# Analog_Buffer.net
KiCad netlist of a schematic drawn in Altium Designer
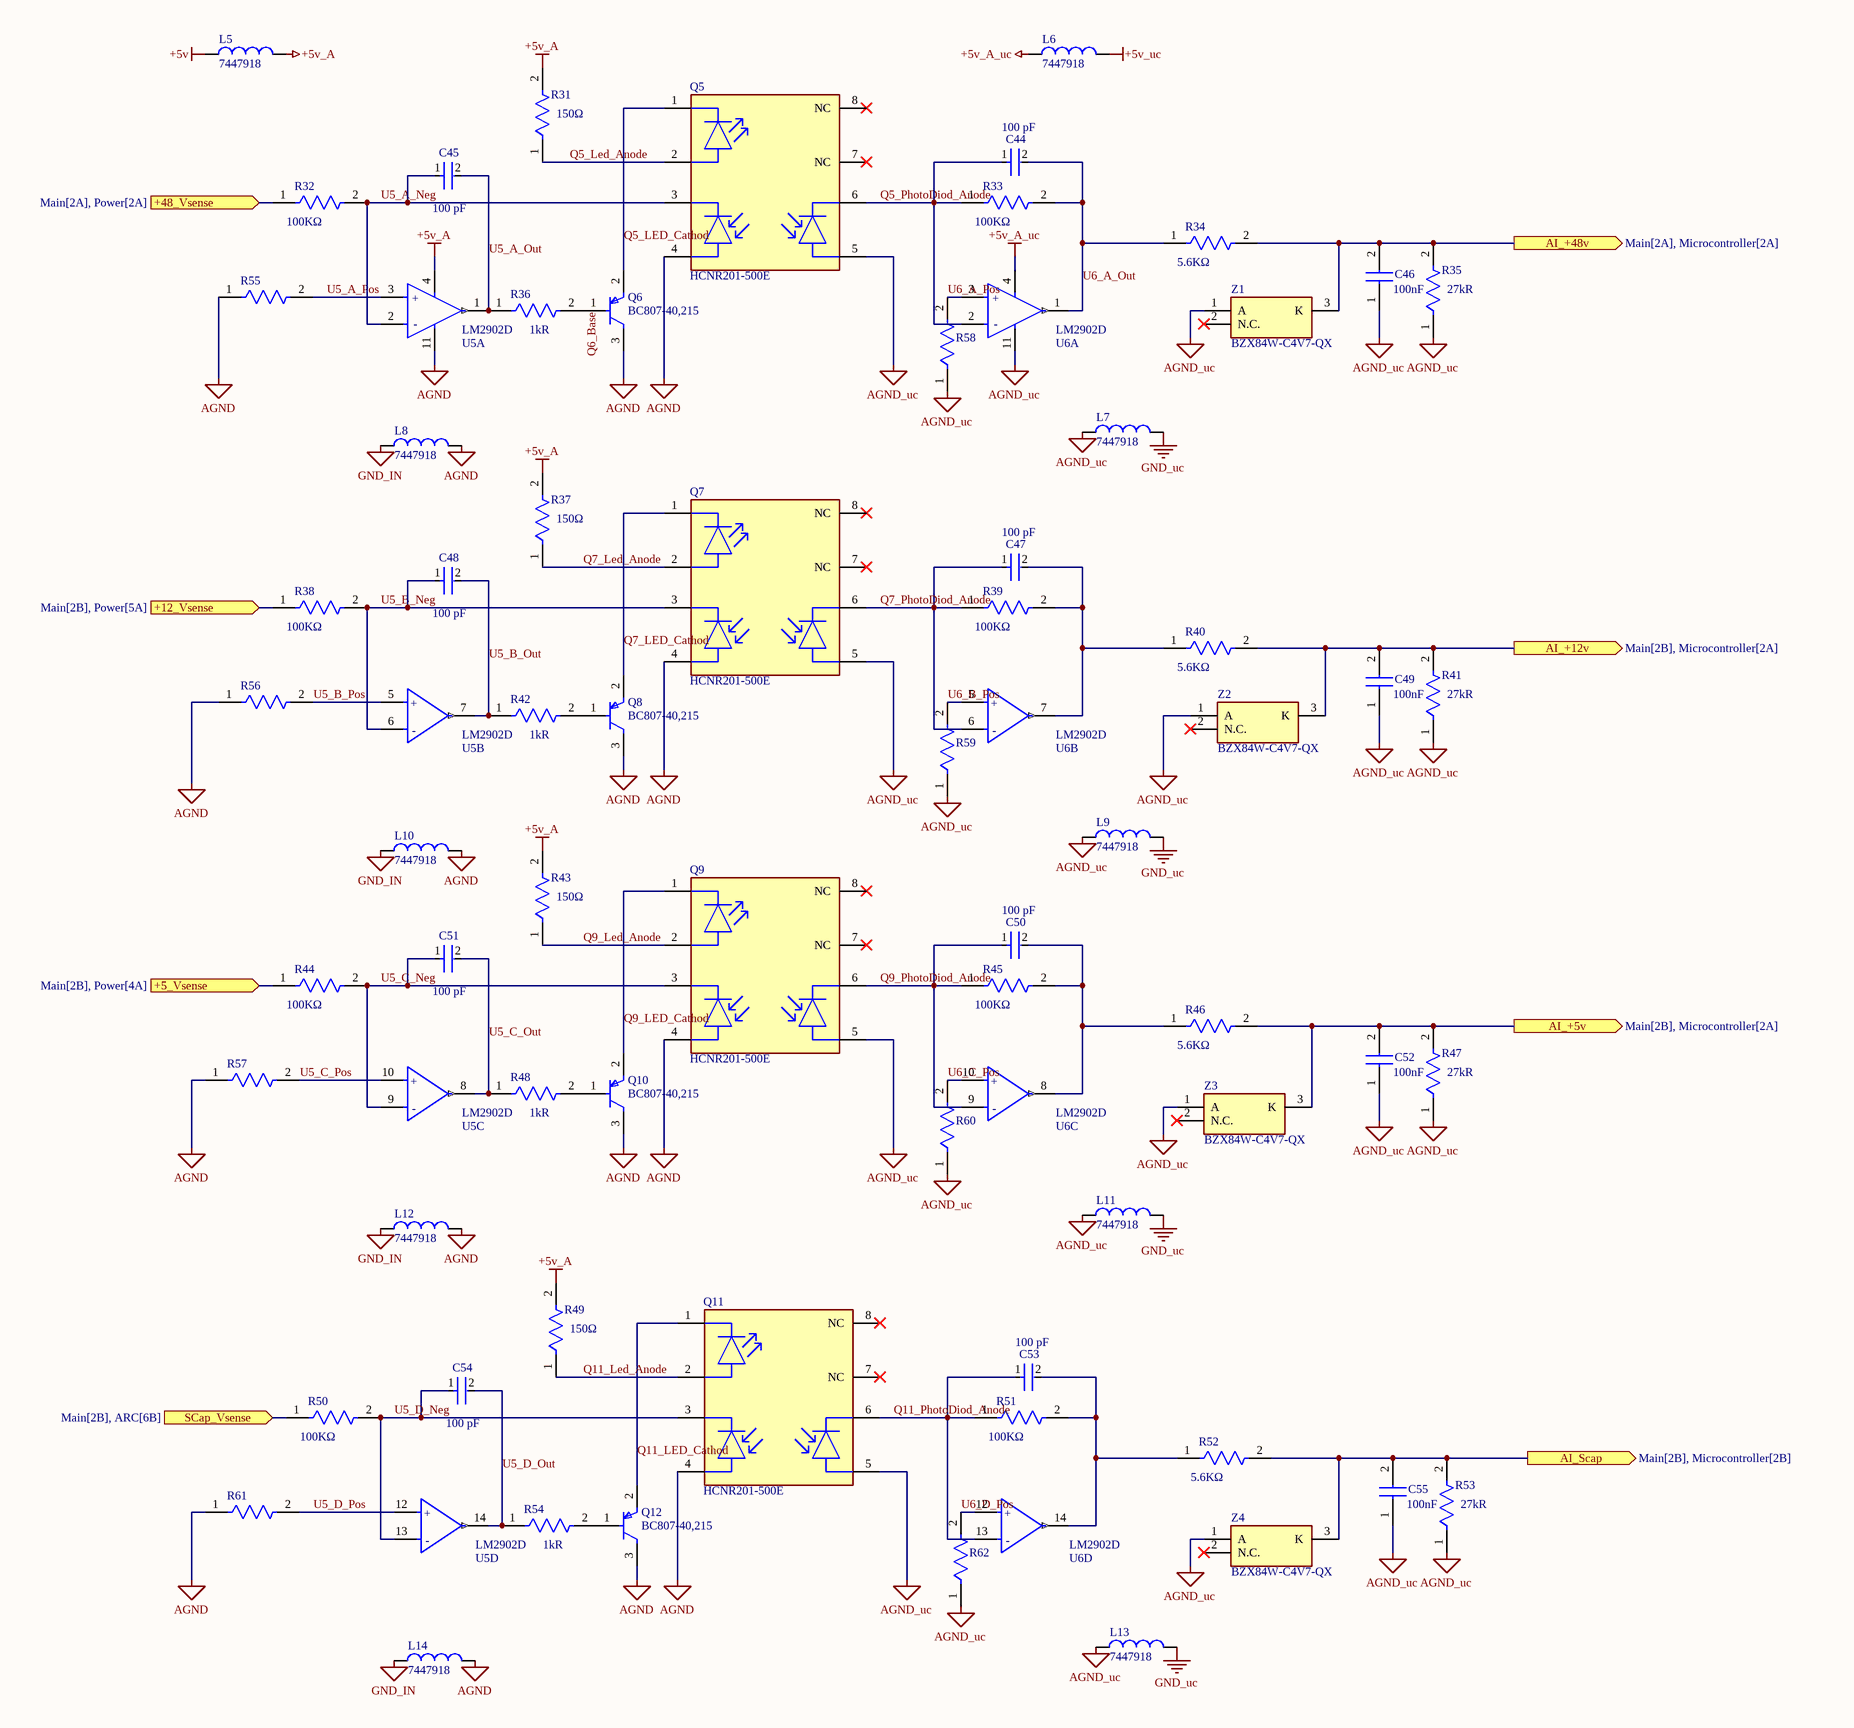
[diagram p0: Analog_Buffer.SchDoc]

(export (version "E")
  (design (tool "Eeschema 10.0.6"))
  (components
    (comp (ref "C44")
      (value "100 pF")
      (footprint "FP-C1206C-EB-MFG")
      (description "CAP CER 100PF 50V 10% NP0 1206")
      (fields
        (field (name "OCTOPART") "https://octopart.com/c1206c101k5gactu-kemet-9138650")
        (field (name "TOLERANCE") "0.1")
      )
      (libsource (lib "Altium Content Vault") (part "b4654b650e69147ec39a6b967a45e02"))
    )
    (comp (ref "C45")
      (value "100 pF")
      (footprint "FP-C1206C-EB-MFG")
      (description "CAP CER 100PF 50V 10% NP0 1206")
      (fields
        (field (name "OCTOPART") "https://octopart.com/c1206c101k5gactu-kemet-9138650")
        (field (name "TOLERANCE") "0.1")
      )
      (libsource (lib "Altium Content Vault") (part "b4654b650e69147ec39a6b967a45e02"))
    )
    (comp (ref "C46")
      (value "100nF")
      (footprint "SamacSys:CAPC3216X95N")
      (description "Capacitor")
      (fields
        (field (name "MANUFACTURER_PART_NUMBER") "GRM319F51H104ZA01D")
        (field (name "MOUSER PART NUMBER") "81-GRM319F51H104ZA")
      )
      (libsource (lib "*") (part "GRM319F51H104ZA01D"))
    )
    (comp (ref "C47")
      (value "100 pF")
      (footprint "FP-C1206C-EB-MFG")
      (description "CAP CER 100PF 50V 10% NP0 1206")
      (fields
        (field (name "OCTOPART") "https://octopart.com/c1206c101k5gactu-kemet-9138650")
        (field (name "TOLERANCE") "0.1")
      )
      (libsource (lib "Altium Content Vault") (part "b4654b650e69147ec39a6b967a45e02"))
    )
    (comp (ref "C48")
      (value "100 pF")
      (footprint "FP-C1206C-EB-MFG")
      (description "CAP CER 100PF 50V 10% NP0 1206")
      (fields
        (field (name "OCTOPART") "https://octopart.com/c1206c101k5gactu-kemet-9138650")
        (field (name "TOLERANCE") "0.1")
      )
      (libsource (lib "Altium Content Vault") (part "b4654b650e69147ec39a6b967a45e02"))
    )
    (comp (ref "C49")
      (value "100nF")
      (footprint "SamacSys:CAPC3216X95N")
      (description "Capacitor")
      (fields
        (field (name "MANUFACTURER_PART_NUMBER") "GRM319F51H104ZA01D")
        (field (name "MOUSER PART NUMBER") "81-GRM319F51H104ZA")
      )
      (libsource (lib "*") (part "GRM319F51H104ZA01D"))
    )
    (comp (ref "C50")
      (value "100 pF")
      (footprint "FP-C1206C-EB-MFG")
      (description "CAP CER 100PF 50V 10% NP0 1206")
      (fields
        (field (name "OCTOPART") "https://octopart.com/c1206c101k5gactu-kemet-9138650")
        (field (name "TOLERANCE") "0.1")
      )
      (libsource (lib "Altium Content Vault") (part "b4654b650e69147ec39a6b967a45e02"))
    )
    (comp (ref "C51")
      (value "100 pF")
      (footprint "FP-C1206C-EB-MFG")
      (description "CAP CER 100PF 50V 10% NP0 1206")
      (fields
        (field (name "OCTOPART") "https://octopart.com/c1206c101k5gactu-kemet-9138650")
        (field (name "TOLERANCE") "0.1")
      )
      (libsource (lib "Altium Content Vault") (part "b4654b650e69147ec39a6b967a45e02"))
    )
    (comp (ref "C52")
      (value "100nF")
      (footprint "SamacSys:CAPC3216X95N")
      (description "Capacitor")
      (fields
        (field (name "MANUFACTURER_PART_NUMBER") "GRM319F51H104ZA01D")
        (field (name "MOUSER PART NUMBER") "81-GRM319F51H104ZA")
      )
      (libsource (lib "*") (part "GRM319F51H104ZA01D"))
    )
    (comp (ref "C53")
      (value "100 pF")
      (footprint "FP-C1206C-EB-MFG")
      (description "CAP CER 100PF 50V 10% NP0 1206")
      (fields
        (field (name "OCTOPART") "https://octopart.com/c1206c101k5gactu-kemet-9138650")
        (field (name "TOLERANCE") "0.1")
      )
      (libsource (lib "Altium Content Vault") (part "b4654b650e69147ec39a6b967a45e02"))
    )
    (comp (ref "C54")
      (value "100 pF")
      (footprint "FP-C1206C-EB-MFG")
      (description "CAP CER 100PF 50V 10% NP0 1206")
      (fields
        (field (name "OCTOPART") "https://octopart.com/c1206c101k5gactu-kemet-9138650")
        (field (name "TOLERANCE") "0.1")
      )
      (libsource (lib "Altium Content Vault") (part "b4654b650e69147ec39a6b967a45e02"))
    )
    (comp (ref "C55")
      (value "100nF")
      (footprint "SamacSys:CAPC3216X95N")
      (description "Capacitor")
      (fields
        (field (name "MANUFACTURER_PART_NUMBER") "GRM319F51H104ZA01D")
        (field (name "MOUSER PART NUMBER") "81-GRM319F51H104ZA")
      )
      (libsource (lib "*") (part "GRM319F51H104ZA01D"))
    )
    (comp (ref "L5")
      (value "7447918")
      (footprint "WE-MI_1206_L3.2W1.6H1.1")
      (fields (field (name "TOLERANCE") "10%"))
      (libsource (lib "Altium Content Vault") (part "Inductor - 1"))
    )
    (comp (ref "L6")
      (value "7447918")
      (footprint "WE-MI_1206_L3.2W1.6H1.1")
      (fields (field (name "TOLERANCE") "10%"))
      (libsource (lib "Altium Content Vault") (part "Inductor - 1"))
    )
    (comp (ref "L7")
      (value "7447918")
      (footprint "WE-MI_1206_L3.2W1.6H1.1")
      (fields (field (name "TOLERANCE") "10%"))
      (libsource (lib "Altium Content Vault") (part "Inductor - 1"))
    )
    (comp (ref "L8")
      (value "7447918")
      (footprint "WE-MI_1206_L3.2W1.6H1.1")
      (fields (field (name "TOLERANCE") "10%"))
      (libsource (lib "Altium Content Vault") (part "Inductor - 1"))
    )
    (comp (ref "L9")
      (value "7447918")
      (footprint "WE-MI_1206_L3.2W1.6H1.1")
      (fields (field (name "TOLERANCE") "10%"))
      (libsource (lib "Altium Content Vault") (part "Inductor - 1"))
    )
    (comp (ref "L10")
      (value "7447918")
      (footprint "WE-MI_1206_L3.2W1.6H1.1")
      (fields (field (name "TOLERANCE") "10%"))
      (libsource (lib "Altium Content Vault") (part "Inductor - 1"))
    )
    (comp (ref "L11")
      (value "7447918")
      (footprint "WE-MI_1206_L3.2W1.6H1.1")
      (fields (field (name "TOLERANCE") "10%"))
      (libsource (lib "Altium Content Vault") (part "Inductor - 1"))
    )
    (comp (ref "L12")
      (value "7447918")
      (footprint "WE-MI_1206_L3.2W1.6H1.1")
      (fields (field (name "TOLERANCE") "10%"))
      (libsource (lib "Altium Content Vault") (part "Inductor - 1"))
    )
    (comp (ref "L13")
      (value "7447918")
      (footprint "WE-MI_1206_L3.2W1.6H1.1")
      (fields (field (name "TOLERANCE") "10%"))
      (libsource (lib "Altium Content Vault") (part "Inductor - 1"))
    )
    (comp (ref "L14")
      (value "7447918")
      (footprint "WE-MI_1206_L3.2W1.6H1.1")
      (fields (field (name "TOLERANCE") "10%"))
      (libsource (lib "Altium Content Vault") (part "Inductor - 1"))
    )
    (comp (ref "Q5")
      (value "HCNR201-500E")
      (footprint "FP-HCNR201-500E-MFG")
      (description "OPTOISO 5KV LINEAR PHVOLT 8DIPGW")
      (libsource (lib "Altium Content Vault") (part "91ab35065b22d0708acdc738a14b8cf"))
    )
    (comp (ref "Q6")
      (value "BC807-40,215")
      (footprint "FP-SOT23-IPC_B")
      (description "TRANS PNP 45V 500MA TO236AB")
      (libsource (lib "Altium Content Vault") (part "0e8486ed3b47d9c69b8404ba87cf0f7"))
    )
    (comp (ref "Q7")
      (value "HCNR201-500E")
      (footprint "FP-HCNR201-500E-MFG")
      (description "OPTOISO 5KV LINEAR PHVOLT 8DIPGW")
      (libsource (lib "Altium Content Vault") (part "91ab35065b22d0708acdc738a14b8cf"))
    )
    (comp (ref "Q8")
      (value "BC807-40,215")
      (footprint "FP-SOT23-IPC_B")
      (description "TRANS PNP 45V 500MA TO236AB")
      (libsource (lib "Altium Content Vault") (part "0e8486ed3b47d9c69b8404ba87cf0f7"))
    )
    (comp (ref "Q9")
      (value "HCNR201-500E")
      (footprint "FP-HCNR201-500E-MFG")
      (description "OPTOISO 5KV LINEAR PHVOLT 8DIPGW")
      (libsource (lib "Altium Content Vault") (part "91ab35065b22d0708acdc738a14b8cf"))
    )
    (comp (ref "Q10")
      (value "BC807-40,215")
      (footprint "FP-SOT23-IPC_B")
      (description "TRANS PNP 45V 500MA TO236AB")
      (libsource (lib "Altium Content Vault") (part "0e8486ed3b47d9c69b8404ba87cf0f7"))
    )
    (comp (ref "Q11")
      (value "HCNR201-500E")
      (footprint "FP-HCNR201-500E-MFG")
      (description "OPTOISO 5KV LINEAR PHVOLT 8DIPGW")
      (libsource (lib "Altium Content Vault") (part "91ab35065b22d0708acdc738a14b8cf"))
    )
    (comp (ref "Q12")
      (value "BC807-40,215")
      (footprint "FP-SOT23-IPC_B")
      (description "TRANS PNP 45V 500MA TO236AB")
      (libsource (lib "Altium Content Vault") (part "0e8486ed3b47d9c69b8404ba87cf0f7"))
    )
    (comp (ref "R31")
      (value "RP73D2B150RBTG")
      (footprint "FP-RP732B-MFG")
      (description "Res Thin Film 1206 150Ω 0.1% 0.25W 15ppm/°C Molded SMD")
      (fields
        (field (name "MANUFACTURER") "TE Connectivity")
        (field (name "RESISTANCE") "150Ω")
        (field (name "TOLERANCE") "0.1%")
      )
      (libsource (lib "Altium Content Vault") (part "1029c3af85768c4190bb7ad29bc67b5"))
    )
    (comp (ref "R32")
      (value "100KΩ")
      (footprint "FP-RT1206-MFG")
      (description "RES SMD 100K OHM 0.5% 1/4W 1206")
      (fields
        (field (name "MANUFACTURER") "Yageo")
        (field (name "OCTOPART") "https://octopart.com/rt1206dre07100kl-yageo-1189867")
      )
      (libsource (lib "Altium Content Vault") (part "1029c3af85768c4190bb7ad29bc67b5"))
    )
    (comp (ref "R33")
      (value "100KΩ")
      (footprint "FP-RT1206-MFG")
      (description "RES SMD 100K OHM 0.5% 1/4W 1206")
      (fields
        (field (name "MANUFACTURER") "Yageo")
        (field (name "OCTOPART") "https://octopart.com/rt1206dre07100kl-yageo-1189867")
      )
      (libsource (lib "Altium Content Vault") (part "1029c3af85768c4190bb7ad29bc67b5"))
    )
    (comp (ref "R34")
      (value "5.6KΩ")
      (footprint "FP-CRGP1206-IPC_C")
      (description "CRGP 1206 5K6 1%")
      (fields (field (name "TOLERANCE") "0.01") (field (name "MANUFACTURER PART NUMBER") "CRGP1206F5K6"))
      (libsource (lib "Altium Content Vault") (part "1029c3af85768c4190bb7ad29bc67b5"))
    )
    (comp (ref "R35")
      (value "RC3216J273CS")
      (footprint "FP-RC3216-IPC_A")
      (description "Res Thick Film 1206 27kΩ 5% 0.25W ±100ppm/°C Molded SMD T/R")
      (fields (field (name "TOLERANCE") "5%") (field (name "RESISTANCE") "27kR"))
      (libsource (lib "Altium Content Vault") (part "1029c3af85768c4190bb7ad29bc67b5"))
    )
    (comp (ref "R36")
      (value "CR1206-FX-1001ELF")
      (footprint "FP-CR1206-IPC_A")
      (description "Thick Film Chip Resistors 1206 1kΩ 0.25W 1% 100ppm/°C")
      (fields (field (name "TOLERANCE") "1%") (field (name "RESISTANCE") "1kR"))
      (libsource (lib "Altium Content Vault") (part "1029c3af85768c4190bb7ad29bc67b5"))
    )
    (comp (ref "R37")
      (value "RP73D2B150RBTG")
      (footprint "FP-RP732B-MFG")
      (description "Res Thin Film 1206 150Ω 0.1% 0.25W 15ppm/°C Molded SMD")
      (fields
        (field (name "MANUFACTURER") "TE Connectivity")
        (field (name "RESISTANCE") "150Ω")
        (field (name "TOLERANCE") "0.1%")
      )
      (libsource (lib "Altium Content Vault") (part "1029c3af85768c4190bb7ad29bc67b5"))
    )
    (comp (ref "R38")
      (value "100KΩ")
      (footprint "FP-RT1206-MFG")
      (description "RES SMD 100K OHM 0.5% 1/4W 1206")
      (fields
        (field (name "MANUFACTURER") "Yageo")
        (field (name "OCTOPART") "https://octopart.com/rt1206dre07100kl-yageo-1189867")
      )
      (libsource (lib "Altium Content Vault") (part "1029c3af85768c4190bb7ad29bc67b5"))
    )
    (comp (ref "R39")
      (value "100KΩ")
      (footprint "FP-RT1206-MFG")
      (description "RES SMD 100K OHM 0.5% 1/4W 1206")
      (fields
        (field (name "MANUFACTURER") "Yageo")
        (field (name "OCTOPART") "https://octopart.com/rt1206dre07100kl-yageo-1189867")
      )
      (libsource (lib "Altium Content Vault") (part "1029c3af85768c4190bb7ad29bc67b5"))
    )
    (comp (ref "R40")
      (value "5.6KΩ")
      (footprint "FP-CRGP1206-IPC_C")
      (description "CRGP 1206 5K6 1%")
      (fields (field (name "TOLERANCE") "0.01") (field (name "MANUFACTURER PART NUMBER") "CRGP1206F5K6"))
      (libsource (lib "Altium Content Vault") (part "1029c3af85768c4190bb7ad29bc67b5"))
    )
    (comp (ref "R41")
      (value "RC3216J273CS")
      (footprint "FP-RC3216-IPC_A")
      (description "Res Thick Film 1206 27kΩ 5% 0.25W ±100ppm/°C Molded SMD T/R")
      (fields (field (name "TOLERANCE") "5%") (field (name "RESISTANCE") "27kR"))
      (libsource (lib "Altium Content Vault") (part "1029c3af85768c4190bb7ad29bc67b5"))
    )
    (comp (ref "R42")
      (value "CR1206-FX-1001ELF")
      (footprint "FP-CR1206-IPC_A")
      (description "Thick Film Chip Resistors 1206 1kΩ 0.25W 1% 100ppm/°C")
      (fields (field (name "TOLERANCE") "1%") (field (name "RESISTANCE") "1kR"))
      (libsource (lib "Altium Content Vault") (part "1029c3af85768c4190bb7ad29bc67b5"))
    )
    (comp (ref "R43")
      (value "RP73D2B150RBTG")
      (footprint "FP-RP732B-MFG")
      (description "Res Thin Film 1206 150Ω 0.1% 0.25W 15ppm/°C Molded SMD")
      (fields
        (field (name "MANUFACTURER") "TE Connectivity")
        (field (name "RESISTANCE") "150Ω")
        (field (name "TOLERANCE") "0.1%")
      )
      (libsource (lib "Altium Content Vault") (part "1029c3af85768c4190bb7ad29bc67b5"))
    )
    (comp (ref "R44")
      (value "100KΩ")
      (footprint "FP-RT1206-MFG")
      (description "RES SMD 100K OHM 0.5% 1/4W 1206")
      (fields
        (field (name "MANUFACTURER") "Yageo")
        (field (name "OCTOPART") "https://octopart.com/rt1206dre07100kl-yageo-1189867")
      )
      (libsource (lib "Altium Content Vault") (part "1029c3af85768c4190bb7ad29bc67b5"))
    )
    (comp (ref "R45")
      (value "100KΩ")
      (footprint "FP-RT1206-MFG")
      (description "RES SMD 100K OHM 0.5% 1/4W 1206")
      (fields
        (field (name "MANUFACTURER") "Yageo")
        (field (name "OCTOPART") "https://octopart.com/rt1206dre07100kl-yageo-1189867")
      )
      (libsource (lib "Altium Content Vault") (part "1029c3af85768c4190bb7ad29bc67b5"))
    )
    (comp (ref "R46")
      (value "5.6KΩ")
      (footprint "FP-CRGP1206-IPC_C")
      (description "CRGP 1206 5K6 1%")
      (fields (field (name "TOLERANCE") "0.01") (field (name "MANUFACTURER PART NUMBER") "CRGP1206F5K6"))
      (libsource (lib "Altium Content Vault") (part "1029c3af85768c4190bb7ad29bc67b5"))
    )
    (comp (ref "R47")
      (value "RC3216J273CS")
      (footprint "FP-RC3216-IPC_A")
      (description "Res Thick Film 1206 27kΩ 5% 0.25W ±100ppm/°C Molded SMD T/R")
      (fields (field (name "TOLERANCE") "5%") (field (name "RESISTANCE") "27kR"))
      (libsource (lib "Altium Content Vault") (part "1029c3af85768c4190bb7ad29bc67b5"))
    )
    (comp (ref "R48")
      (value "CR1206-FX-1001ELF")
      (footprint "FP-CR1206-IPC_A")
      (description "Thick Film Chip Resistors 1206 1kΩ 0.25W 1% 100ppm/°C")
      (fields (field (name "TOLERANCE") "1%") (field (name "RESISTANCE") "1kR"))
      (libsource (lib "Altium Content Vault") (part "1029c3af85768c4190bb7ad29bc67b5"))
    )
    (comp (ref "R49")
      (value "RP73D2B150RBTG")
      (footprint "FP-RP732B-MFG")
      (description "Res Thin Film 1206 150Ω 0.1% 0.25W 15ppm/°C Molded SMD")
      (fields
        (field (name "MANUFACTURER") "TE Connectivity")
        (field (name "RESISTANCE") "150Ω")
        (field (name "TOLERANCE") "0.1%")
      )
      (libsource (lib "Altium Content Vault") (part "1029c3af85768c4190bb7ad29bc67b5"))
    )
    (comp (ref "R50")
      (value "100KΩ")
      (footprint "FP-RT1206-MFG")
      (description "RES SMD 100K OHM 0.5% 1/4W 1206")
      (fields
        (field (name "MANUFACTURER") "Yageo")
        (field (name "OCTOPART") "https://octopart.com/rt1206dre07100kl-yageo-1189867")
      )
      (libsource (lib "Altium Content Vault") (part "1029c3af85768c4190bb7ad29bc67b5"))
    )
    (comp (ref "R51")
      (value "100KΩ")
      (footprint "FP-RT1206-MFG")
      (description "RES SMD 100K OHM 0.5% 1/4W 1206")
      (fields
        (field (name "MANUFACTURER") "Yageo")
        (field (name "OCTOPART") "https://octopart.com/rt1206dre07100kl-yageo-1189867")
      )
      (libsource (lib "Altium Content Vault") (part "1029c3af85768c4190bb7ad29bc67b5"))
    )
    (comp (ref "R52")
      (value "5.6KΩ")
      (footprint "FP-CRGP1206-IPC_C")
      (description "CRGP 1206 5K6 1%")
      (fields (field (name "TOLERANCE") "0.01") (field (name "MANUFACTURER PART NUMBER") "CRGP1206F5K6"))
      (libsource (lib "Altium Content Vault") (part "1029c3af85768c4190bb7ad29bc67b5"))
    )
    (comp (ref "R53")
      (value "RC3216J273CS")
      (footprint "FP-RC3216-IPC_A")
      (description "Res Thick Film 1206 27kΩ 5% 0.25W ±100ppm/°C Molded SMD T/R")
      (fields (field (name "TOLERANCE") "5%") (field (name "RESISTANCE") "27kR"))
      (libsource (lib "Altium Content Vault") (part "1029c3af85768c4190bb7ad29bc67b5"))
    )
    (comp (ref "R54")
      (value "CR1206-FX-1001ELF")
      (footprint "FP-CR1206-IPC_A")
      (description "Thick Film Chip Resistors 1206 1kΩ 0.25W 1% 100ppm/°C")
      (fields (field (name "TOLERANCE") "1%") (field (name "RESISTANCE") "1kR"))
      (libsource (lib "Altium Content Vault") (part "1029c3af85768c4190bb7ad29bc67b5"))
    )
    (comp (ref "R55")
      (value "RC1206JR-070RL")
      (footprint "FP-RC1206-MFG")
      (description "RES SMD 0 OHM JUMPER 1/4W 1206")
      (fields
        (field (name "MANUFACTURER") "YAGEO")
        (field (name "OCTOPART") "https://octopart.com/rc1206jr-070rl-yageo-40025601")
      )
      (libsource (lib "Altium Content Vault") (part "1029c3af85768c4190bb7ad29bc67b5"))
    )
    (comp (ref "R56")
      (value "RC1206JR-070RL")
      (footprint "FP-RC1206-MFG")
      (description "RES SMD 0 OHM JUMPER 1/4W 1206")
      (fields
        (field (name "MANUFACTURER") "YAGEO")
        (field (name "OCTOPART") "https://octopart.com/rc1206jr-070rl-yageo-40025601")
      )
      (libsource (lib "Altium Content Vault") (part "1029c3af85768c4190bb7ad29bc67b5"))
    )
    (comp (ref "R57")
      (value "RC1206JR-070RL")
      (footprint "FP-RC1206-MFG")
      (description "RES SMD 0 OHM JUMPER 1/4W 1206")
      (fields
        (field (name "MANUFACTURER") "YAGEO")
        (field (name "OCTOPART") "https://octopart.com/rc1206jr-070rl-yageo-40025601")
      )
      (libsource (lib "Altium Content Vault") (part "1029c3af85768c4190bb7ad29bc67b5"))
    )
    (comp (ref "R58")
      (value "RC1206JR-070RL")
      (footprint "FP-RC1206-MFG")
      (description "RES SMD 0 OHM JUMPER 1/4W 1206")
      (fields
        (field (name "MANUFACTURER") "YAGEO")
        (field (name "OCTOPART") "https://octopart.com/rc1206jr-070rl-yageo-40025601")
      )
      (libsource (lib "Altium Content Vault") (part "1029c3af85768c4190bb7ad29bc67b5"))
    )
    (comp (ref "R59")
      (value "RC1206JR-070RL")
      (footprint "FP-RC1206-MFG")
      (description "RES SMD 0 OHM JUMPER 1/4W 1206")
      (fields
        (field (name "MANUFACTURER") "YAGEO")
        (field (name "OCTOPART") "https://octopart.com/rc1206jr-070rl-yageo-40025601")
      )
      (libsource (lib "Altium Content Vault") (part "1029c3af85768c4190bb7ad29bc67b5"))
    )
    (comp (ref "R60")
      (value "RC1206JR-070RL")
      (footprint "FP-RC1206-MFG")
      (description "RES SMD 0 OHM JUMPER 1/4W 1206")
      (fields
        (field (name "MANUFACTURER") "YAGEO")
        (field (name "OCTOPART") "https://octopart.com/rc1206jr-070rl-yageo-40025601")
      )
      (libsource (lib "Altium Content Vault") (part "1029c3af85768c4190bb7ad29bc67b5"))
    )
    (comp (ref "R61")
      (value "RC1206JR-070RL")
      (footprint "FP-RC1206-MFG")
      (description "RES SMD 0 OHM JUMPER 1/4W 1206")
      (fields
        (field (name "MANUFACTURER") "YAGEO")
        (field (name "OCTOPART") "https://octopart.com/rc1206jr-070rl-yageo-40025601")
      )
      (libsource (lib "Altium Content Vault") (part "1029c3af85768c4190bb7ad29bc67b5"))
    )
    (comp (ref "R62")
      (value "RC1206JR-070RL")
      (footprint "FP-RC1206-MFG")
      (description "RES SMD 0 OHM JUMPER 1/4W 1206")
      (fields
        (field (name "MANUFACTURER") "YAGEO")
        (field (name "OCTOPART") "https://octopart.com/rc1206jr-070rl-yageo-40025601")
      )
      (libsource (lib "Altium Content Vault") (part "1029c3af85768c4190bb7ad29bc67b5"))
    )
    (comp (ref "U5")
      (value "LM2902D")
      (footprint "FP-D0014A-MFG")
      (description "IC OPAMP GP 4 CIRCUIT 14SOIC")
      (libsource (lib "Altium Content Vault") (part "b02d0cb41c0d90ddc6f34c0e90b5c12"))
    )
    (comp (ref "U6")
      (value "LM2902D")
      (footprint "FP-D0014A-MFG")
      (description "IC OPAMP GP 4 CIRCUIT 14SOIC")
      (libsource (lib "Altium Content Vault") (part "b02d0cb41c0d90ddc6f34c0e90b5c12"))
    )
    (comp (ref "Z1")
      (value "BZX84W-C4V7-QX")
      (footprint "SamacSys:SOT65P210X110-3N")
      (description "Zener Diode")
      (libsource (lib "*") (part "BZX84W-C4V7-QX"))
    )
    (comp (ref "Z2")
      (value "BZX84W-C4V7-QX")
      (footprint "SamacSys:SOT65P210X110-3N")
      (description "Zener Diode")
      (libsource (lib "*") (part "BZX84W-C4V7-QX"))
    )
    (comp (ref "Z3")
      (value "BZX84W-C4V7-QX")
      (footprint "SamacSys:SOT65P210X110-3N")
      (description "Zener Diode")
      (libsource (lib "*") (part "BZX84W-C4V7-QX"))
    )
    (comp (ref "Z4")
      (value "BZX84W-C4V7-QX")
      (footprint "SamacSys:SOT65P210X110-3N")
      (description "Zener Diode")
      (libsource (lib "*") (part "BZX84W-C4V7-QX"))
    )
  )
  (nets
    (net (code "1") (name "+5v") (class "Default")
      (node (ref "L5") (pin "1") (pinfunction "1_1") (pintype "passive"))
    )
    (net (code "2") (name "+5v_A") (class "Default")
      (node (ref "L5") (pin "2") (pinfunction "2_2") (pintype "passive"))
      (node (ref "R31") (pin "2") (pinfunction "2_2") (pintype "passive"))
      (node (ref "R37") (pin "2") (pinfunction "2_2") (pintype "passive"))
      (node (ref "R43") (pin "2") (pinfunction "2_2") (pintype "passive"))
      (node (ref "R49") (pin "2") (pinfunction "2_2") (pintype "passive"))
      (node (ref "U5") (pin "4") (pinfunction "VCC_4") (pintype "power_in"))
    )
    (net (code "3") (name "+5v_A_uc") (class "Default")
      (node (ref "L6") (pin "1") (pinfunction "1_1") (pintype "passive"))
      (node (ref "U6") (pin "4") (pinfunction "VCC_4") (pintype "power_in"))
    )
    (net (code "4") (name "+5v_uc") (class "Default")
      (node (ref "L6") (pin "2") (pinfunction "2_2") (pintype "passive"))
    )
    (net (code "5") (name "/+5_Vsense") (class "Default")
      (node (ref "R44") (pin "1") (pinfunction "1_1") (pintype "passive"))
    )
    (net (code "6") (name "/+12_Vsense") (class "Default")
      (node (ref "R38") (pin "1") (pinfunction "1_1") (pintype "passive"))
    )
    (net (code "7") (name "/+48_Vsense") (class "Default")
      (node (ref "R32") (pin "1") (pinfunction "1_1") (pintype "passive"))
    )
    (net (code "8") (name "/AI_+5v") (class "Default")
      (node (ref "C52") (pin "2") (pinfunction "2_2") (pintype "passive"))
      (node (ref "R46") (pin "2") (pinfunction "2_2") (pintype "passive"))
      (node (ref "R47") (pin "2") (pinfunction "2_2") (pintype "passive"))
      (node (ref "Z3") (pin "3") (pinfunction "K_3") (pintype "passive"))
    )
    (net (code "9") (name "/AI_+12v") (class "Default")
      (node (ref "C49") (pin "2") (pinfunction "2_2") (pintype "passive"))
      (node (ref "R40") (pin "2") (pinfunction "2_2") (pintype "passive"))
      (node (ref "R41") (pin "2") (pinfunction "2_2") (pintype "passive"))
      (node (ref "Z2") (pin "3") (pinfunction "K_3") (pintype "passive"))
    )
    (net (code "10") (name "/AI_+48v") (class "Default")
      (node (ref "C46") (pin "2") (pinfunction "2_2") (pintype "passive"))
      (node (ref "R34") (pin "2") (pinfunction "2_2") (pintype "passive"))
      (node (ref "R35") (pin "2") (pinfunction "2_2") (pintype "passive"))
      (node (ref "Z1") (pin "3") (pinfunction "K_3") (pintype "passive"))
    )
    (net (code "11") (name "/AI_Scap") (class "Default")
      (node (ref "C55") (pin "2") (pinfunction "2_2") (pintype "passive"))
      (node (ref "R52") (pin "2") (pinfunction "2_2") (pintype "passive"))
      (node (ref "R53") (pin "2") (pinfunction "2_2") (pintype "passive"))
      (node (ref "Z4") (pin "3") (pinfunction "K_3") (pintype "passive"))
    )
    (net (code "12") (name "/Q5_LED_Cathod") (class "Default")
      (node (ref "Q5") (pin "1") (pinfunction "LED_CATHODE_1") (pintype "passive"))
      (node (ref "Q6") (pin "2") (pinfunction "E_2") (pintype "passive"))
    )
    (net (code "13") (name "/Q5_Led_Anode") (class "Default")
      (node (ref "Q5") (pin "2") (pinfunction "LED_ANODE_2") (pintype "passive"))
      (node (ref "R31") (pin "1") (pinfunction "1_1") (pintype "passive"))
    )
    (net (code "14") (name "/Q5_PhotoDiod_Anode") (class "Default")
      (node (ref "C44") (pin "1") (pinfunction "1_1") (pintype "passive"))
      (node (ref "Q5") (pin "6") (pinfunction "PD2_CATHODE_6") (pintype "passive"))
      (node (ref "R33") (pin "1") (pinfunction "1_1") (pintype "passive"))
      (node (ref "U6") (pin "2") (pinfunction "1IN-_2") (pintype "tri_state"))
    )
    (net (code "15") (name "/Q6_Base") (class "Default")
      (node (ref "Q6") (pin "1") (pinfunction "B_1") (pintype "passive"))
      (node (ref "R36") (pin "2") (pinfunction "2_2") (pintype "passive"))
    )
    (net (code "16") (name "/Q7_LED_Cathod") (class "Default")
      (node (ref "Q7") (pin "1") (pinfunction "LED_CATHODE_1") (pintype "passive"))
      (node (ref "Q8") (pin "2") (pinfunction "E_2") (pintype "passive"))
    )
    (net (code "17") (name "/Q7_Led_Anode") (class "Default")
      (node (ref "Q7") (pin "2") (pinfunction "LED_ANODE_2") (pintype "passive"))
      (node (ref "R37") (pin "1") (pinfunction "1_1") (pintype "passive"))
    )
    (net (code "18") (name "/Q7_PhotoDiod_Anode") (class "Default")
      (node (ref "C47") (pin "1") (pinfunction "1_1") (pintype "passive"))
      (node (ref "Q7") (pin "6") (pinfunction "PD2_CATHODE_6") (pintype "passive"))
      (node (ref "R39") (pin "1") (pinfunction "1_1") (pintype "passive"))
      (node (ref "U6") (pin "6") (pinfunction "2IN-_6") (pintype "tri_state"))
    )
    (net (code "19") (name "/Q9_LED_Cathod") (class "Default")
      (node (ref "Q10") (pin "2") (pinfunction "E_2") (pintype "passive"))
      (node (ref "Q9") (pin "1") (pinfunction "LED_CATHODE_1") (pintype "passive"))
    )
    (net (code "20") (name "/Q9_Led_Anode") (class "Default")
      (node (ref "Q9") (pin "2") (pinfunction "LED_ANODE_2") (pintype "passive"))
      (node (ref "R43") (pin "1") (pinfunction "1_1") (pintype "passive"))
    )
    (net (code "21") (name "/Q9_PhotoDiod_Anode") (class "Default")
      (node (ref "C50") (pin "1") (pinfunction "1_1") (pintype "passive"))
      (node (ref "Q9") (pin "6") (pinfunction "PD2_CATHODE_6") (pintype "passive"))
      (node (ref "R45") (pin "1") (pinfunction "1_1") (pintype "passive"))
      (node (ref "U6") (pin "9") (pinfunction "3IN-_9") (pintype "tri_state"))
    )
    (net (code "22") (name "/Q11_LED_Cathod") (class "Default")
      (node (ref "Q11") (pin "1") (pinfunction "LED_CATHODE_1") (pintype "passive"))
      (node (ref "Q12") (pin "2") (pinfunction "E_2") (pintype "passive"))
    )
    (net (code "23") (name "/Q11_Led_Anode") (class "Default")
      (node (ref "Q11") (pin "2") (pinfunction "LED_ANODE_2") (pintype "passive"))
      (node (ref "R49") (pin "1") (pinfunction "1_1") (pintype "passive"))
    )
    (net (code "24") (name "/Q11_PhotoDiod_Anode") (class "Default")
      (node (ref "C53") (pin "1") (pinfunction "1_1") (pintype "passive"))
      (node (ref "Q11") (pin "6") (pinfunction "PD2_CATHODE_6") (pintype "passive"))
      (node (ref "R51") (pin "1") (pinfunction "1_1") (pintype "passive"))
      (node (ref "U6") (pin "13") (pinfunction "4IN-_13") (pintype "tri_state"))
    )
    (net (code "25") (name "/SCap_Vsense") (class "Default")
      (node (ref "R50") (pin "1") (pinfunction "1_1") (pintype "passive"))
    )
    (net (code "26") (name "/U5_A_Neg") (class "Default")
      (node (ref "C45") (pin "1") (pinfunction "1_1") (pintype "passive"))
      (node (ref "Q5") (pin "3") (pinfunction "PD1_CATHODE_3") (pintype "passive"))
      (node (ref "R32") (pin "2") (pinfunction "2_2") (pintype "passive"))
      (node (ref "U5") (pin "2") (pinfunction "1IN-_2") (pintype "tri_state"))
    )
    (net (code "27") (name "/U5_A_Out") (class "Default")
      (node (ref "C45") (pin "2") (pinfunction "2_2") (pintype "passive"))
      (node (ref "R36") (pin "1") (pinfunction "1_1") (pintype "passive"))
      (node (ref "U5") (pin "1") (pinfunction "1OUT_1") (pintype "output"))
    )
    (net (code "28") (name "/U5_A_Pos") (class "Default")
      (node (ref "R55") (pin "2") (pinfunction "2_2") (pintype "passive"))
      (node (ref "U5") (pin "3") (pinfunction "1IN+_3") (pintype "tri_state"))
    )
    (net (code "29") (name "/U5_B_Neg") (class "Default")
      (node (ref "C48") (pin "1") (pinfunction "1_1") (pintype "passive"))
      (node (ref "Q7") (pin "3") (pinfunction "PD1_CATHODE_3") (pintype "passive"))
      (node (ref "R38") (pin "2") (pinfunction "2_2") (pintype "passive"))
      (node (ref "U5") (pin "6") (pinfunction "2IN-_6") (pintype "tri_state"))
    )
    (net (code "30") (name "/U5_B_Out") (class "Default")
      (node (ref "C48") (pin "2") (pinfunction "2_2") (pintype "passive"))
      (node (ref "R42") (pin "1") (pinfunction "1_1") (pintype "passive"))
      (node (ref "U5") (pin "7") (pinfunction "2OUT_7") (pintype "output"))
    )
    (net (code "31") (name "/U5_B_Pos") (class "Default")
      (node (ref "R56") (pin "2") (pinfunction "2_2") (pintype "passive"))
      (node (ref "U5") (pin "5") (pinfunction "2IN+_5") (pintype "tri_state"))
    )
    (net (code "32") (name "/U5_C_Neg") (class "Default")
      (node (ref "C51") (pin "1") (pinfunction "1_1") (pintype "passive"))
      (node (ref "Q9") (pin "3") (pinfunction "PD1_CATHODE_3") (pintype "passive"))
      (node (ref "R44") (pin "2") (pinfunction "2_2") (pintype "passive"))
      (node (ref "U5") (pin "9") (pinfunction "3IN-_9") (pintype "tri_state"))
    )
    (net (code "33") (name "/U5_C_Out") (class "Default")
      (node (ref "C51") (pin "2") (pinfunction "2_2") (pintype "passive"))
      (node (ref "R48") (pin "1") (pinfunction "1_1") (pintype "passive"))
      (node (ref "U5") (pin "8") (pinfunction "3OUT_8") (pintype "output"))
    )
    (net (code "34") (name "/U5_C_Pos") (class "Default")
      (node (ref "R57") (pin "2") (pinfunction "2_2") (pintype "passive"))
      (node (ref "U5") (pin "10") (pinfunction "3IN+_10") (pintype "tri_state"))
    )
    (net (code "35") (name "/U5_D_Neg") (class "Default")
      (node (ref "C54") (pin "1") (pinfunction "1_1") (pintype "passive"))
      (node (ref "Q11") (pin "3") (pinfunction "PD1_CATHODE_3") (pintype "passive"))
      (node (ref "R50") (pin "2") (pinfunction "2_2") (pintype "passive"))
      (node (ref "U5") (pin "13") (pinfunction "4IN-_13") (pintype "tri_state"))
    )
    (net (code "36") (name "/U5_D_Out") (class "Default")
      (node (ref "C54") (pin "2") (pinfunction "2_2") (pintype "passive"))
      (node (ref "R54") (pin "1") (pinfunction "1_1") (pintype "passive"))
      (node (ref "U5") (pin "14") (pinfunction "4OUT_14") (pintype "output"))
    )
    (net (code "37") (name "/U5_D_Pos") (class "Default")
      (node (ref "R61") (pin "2") (pinfunction "2_2") (pintype "passive"))
      (node (ref "U5") (pin "12") (pinfunction "4IN+_12") (pintype "tri_state"))
    )
    (net (code "38") (name "/U6_A_Out") (class "Default")
      (node (ref "C44") (pin "2") (pinfunction "2_2") (pintype "passive"))
      (node (ref "R33") (pin "2") (pinfunction "2_2") (pintype "passive"))
      (node (ref "R34") (pin "1") (pinfunction "1_1") (pintype "passive"))
      (node (ref "U6") (pin "1") (pinfunction "1OUT_1") (pintype "output"))
    )
    (net (code "39") (name "/U6_A_Pos") (class "Default")
      (node (ref "R58") (pin "2") (pinfunction "2_2") (pintype "passive"))
      (node (ref "U6") (pin "3") (pinfunction "1IN+_3") (pintype "tri_state"))
    )
    (net (code "40") (name "/U6_B_Pos") (class "Default")
      (node (ref "R59") (pin "2") (pinfunction "2_2") (pintype "passive"))
      (node (ref "U6") (pin "5") (pinfunction "2IN+_5") (pintype "tri_state"))
    )
    (net (code "41") (name "/U6_C_Pos") (class "Default")
      (node (ref "R60") (pin "2") (pinfunction "2_2") (pintype "passive"))
      (node (ref "U6") (pin "10") (pinfunction "3IN+_10") (pintype "tri_state"))
    )
    (net (code "42") (name "/U6_D_Pos") (class "Default")
      (node (ref "R62") (pin "2") (pinfunction "2_2") (pintype "passive"))
      (node (ref "U6") (pin "12") (pinfunction "4IN+_12") (pintype "tri_state"))
    )
    (net (code "43") (name "AGND") (class "Default")
      (node (ref "L10") (pin "2") (pinfunction "2_2") (pintype "passive"))
      (node (ref "L12") (pin "2") (pinfunction "2_2") (pintype "passive"))
      (node (ref "L14") (pin "2") (pinfunction "2_2") (pintype "passive"))
      (node (ref "L8") (pin "2") (pinfunction "2_2") (pintype "passive"))
      (node (ref "Q10") (pin "3") (pinfunction "C_3") (pintype "passive"))
      (node (ref "Q11") (pin "4") (pinfunction "PD1_ANODE_4") (pintype "passive"))
      (node (ref "Q12") (pin "3") (pinfunction "C_3") (pintype "passive"))
      (node (ref "Q5") (pin "4") (pinfunction "PD1_ANODE_4") (pintype "passive"))
      (node (ref "Q6") (pin "3") (pinfunction "C_3") (pintype "passive"))
      (node (ref "Q7") (pin "4") (pinfunction "PD1_ANODE_4") (pintype "passive"))
      (node (ref "Q8") (pin "3") (pinfunction "C_3") (pintype "passive"))
      (node (ref "Q9") (pin "4") (pinfunction "PD1_ANODE_4") (pintype "passive"))
      (node (ref "R55") (pin "1") (pinfunction "1_1") (pintype "passive"))
      (node (ref "R56") (pin "1") (pinfunction "1_1") (pintype "passive"))
      (node (ref "R57") (pin "1") (pinfunction "1_1") (pintype "passive"))
      (node (ref "R61") (pin "1") (pinfunction "1_1") (pintype "passive"))
      (node (ref "U5") (pin "11") (pinfunction "GND_11") (pintype "power_in"))
    )
    (net (code "44") (name "AGND_uc") (class "Default")
      (node (ref "C46") (pin "1") (pinfunction "1_1") (pintype "passive"))
      (node (ref "C49") (pin "1") (pinfunction "1_1") (pintype "passive"))
      (node (ref "C52") (pin "1") (pinfunction "1_1") (pintype "passive"))
      (node (ref "C55") (pin "1") (pinfunction "1_1") (pintype "passive"))
      (node (ref "L11") (pin "1") (pinfunction "1_1") (pintype "passive"))
      (node (ref "L13") (pin "1") (pinfunction "1_1") (pintype "passive"))
      (node (ref "L7") (pin "1") (pinfunction "1_1") (pintype "passive"))
      (node (ref "L9") (pin "1") (pinfunction "1_1") (pintype "passive"))
      (node (ref "Q11") (pin "5") (pinfunction "PD2_ANODE_5") (pintype "passive"))
      (node (ref "Q5") (pin "5") (pinfunction "PD2_ANODE_5") (pintype "passive"))
      (node (ref "Q7") (pin "5") (pinfunction "PD2_ANODE_5") (pintype "passive"))
      (node (ref "Q9") (pin "5") (pinfunction "PD2_ANODE_5") (pintype "passive"))
      (node (ref "R35") (pin "1") (pinfunction "1_1") (pintype "passive"))
      (node (ref "R41") (pin "1") (pinfunction "1_1") (pintype "passive"))
      (node (ref "R47") (pin "1") (pinfunction "1_1") (pintype "passive"))
      (node (ref "R53") (pin "1") (pinfunction "1_1") (pintype "passive"))
      (node (ref "R58") (pin "1") (pinfunction "1_1") (pintype "passive"))
      (node (ref "R59") (pin "1") (pinfunction "1_1") (pintype "passive"))
      (node (ref "R60") (pin "1") (pinfunction "1_1") (pintype "passive"))
      (node (ref "R62") (pin "1") (pinfunction "1_1") (pintype "passive"))
      (node (ref "U6") (pin "11") (pinfunction "GND_11") (pintype "power_in"))
      (node (ref "Z1") (pin "1") (pinfunction "A_1") (pintype "passive"))
      (node (ref "Z2") (pin "1") (pinfunction "A_1") (pintype "passive"))
      (node (ref "Z3") (pin "1") (pinfunction "A_1") (pintype "passive"))
      (node (ref "Z4") (pin "1") (pinfunction "A_1") (pintype "passive"))
    )
    (net (code "45") (name "GND_IN") (class "Default")
      (node (ref "L10") (pin "1") (pinfunction "1_1") (pintype "passive"))
      (node (ref "L12") (pin "1") (pinfunction "1_1") (pintype "passive"))
      (node (ref "L14") (pin "1") (pinfunction "1_1") (pintype "passive"))
      (node (ref "L8") (pin "1") (pinfunction "1_1") (pintype "passive"))
    )
    (net (code "46") (name "GND_uc") (class "Default")
      (node (ref "L11") (pin "2") (pinfunction "2_2") (pintype "passive"))
      (node (ref "L13") (pin "2") (pinfunction "2_2") (pintype "passive"))
      (node (ref "L7") (pin "2") (pinfunction "2_2") (pintype "passive"))
      (node (ref "L9") (pin "2") (pinfunction "2_2") (pintype "passive"))
    )
    (net (code "47") (name "Net-(Q8-B)") (class "Default")
      (node (ref "Q8") (pin "1") (pinfunction "B_1") (pintype "passive"))
      (node (ref "R42") (pin "2") (pinfunction "2_2") (pintype "passive"))
    )
    (net (code "48") (name "Net-(Q10-B)") (class "Default")
      (node (ref "Q10") (pin "1") (pinfunction "B_1") (pintype "passive"))
      (node (ref "R48") (pin "2") (pinfunction "2_2") (pintype "passive"))
    )
    (net (code "49") (name "Net-(Q12-B)") (class "Default")
      (node (ref "Q12") (pin "1") (pinfunction "B_1") (pintype "passive"))
      (node (ref "R54") (pin "2") (pinfunction "2_2") (pintype "passive"))
    )
    (net (code "50") (name "Net-(U6B-2OUT)") (class "Default")
      (node (ref "C47") (pin "2") (pinfunction "2_2") (pintype "passive"))
      (node (ref "R39") (pin "2") (pinfunction "2_2") (pintype "passive"))
      (node (ref "R40") (pin "1") (pinfunction "1_1") (pintype "passive"))
      (node (ref "U6") (pin "7") (pinfunction "2OUT_7") (pintype "output"))
    )
    (net (code "51") (name "Net-(U6C-3OUT)") (class "Default")
      (node (ref "C50") (pin "2") (pinfunction "2_2") (pintype "passive"))
      (node (ref "R45") (pin "2") (pinfunction "2_2") (pintype "passive"))
      (node (ref "R46") (pin "1") (pinfunction "1_1") (pintype "passive"))
      (node (ref "U6") (pin "8") (pinfunction "3OUT_8") (pintype "output"))
    )
    (net (code "52") (name "Net-(U6D-4OUT)") (class "Default")
      (node (ref "C53") (pin "2") (pinfunction "2_2") (pintype "passive"))
      (node (ref "R51") (pin "2") (pinfunction "2_2") (pintype "passive"))
      (node (ref "R52") (pin "1") (pinfunction "1_1") (pintype "passive"))
      (node (ref "U6") (pin "14") (pinfunction "4OUT_14") (pintype "output"))
    )
    (net (code "53") (name "unconnected-(Q5-NC-Pad7)") (class "Default")
      (node (ref "Q5") (pin "7") (pinfunction "NC_7") (pintype "passive+no_connect"))
    )
    (net (code "54") (name "unconnected-(Q5-NC-Pad8)") (class "Default")
      (node (ref "Q5") (pin "8") (pinfunction "NC_8") (pintype "passive+no_connect"))
    )
    (net (code "55") (name "unconnected-(Q7-NC-Pad7)") (class "Default")
      (node (ref "Q7") (pin "7") (pinfunction "NC_7") (pintype "passive+no_connect"))
    )
    (net (code "56") (name "unconnected-(Q7-NC-Pad8)") (class "Default")
      (node (ref "Q7") (pin "8") (pinfunction "NC_8") (pintype "passive+no_connect"))
    )
    (net (code "57") (name "unconnected-(Q9-NC-Pad7)") (class "Default")
      (node (ref "Q9") (pin "7") (pinfunction "NC_7") (pintype "passive+no_connect"))
    )
    (net (code "58") (name "unconnected-(Q9-NC-Pad8)") (class "Default")
      (node (ref "Q9") (pin "8") (pinfunction "NC_8") (pintype "passive+no_connect"))
    )
    (net (code "59") (name "unconnected-(Q11-NC-Pad7)") (class "Default")
      (node (ref "Q11") (pin "7") (pinfunction "NC_7") (pintype "passive+no_connect"))
    )
    (net (code "60") (name "unconnected-(Q11-NC-Pad8)") (class "Default")
      (node (ref "Q11") (pin "8") (pinfunction "NC_8") (pintype "passive+no_connect"))
    )
    (net (code "61") (name "unconnected-(Z1-N.C.-Pad2)") (class "Default")
      (node (ref "Z1") (pin "2") (pinfunction "N.C._2") (pintype "passive+no_connect"))
    )
    (net (code "62") (name "unconnected-(Z2-N.C.-Pad2)") (class "Default")
      (node (ref "Z2") (pin "2") (pinfunction "N.C._2") (pintype "passive+no_connect"))
    )
    (net (code "63") (name "unconnected-(Z3-N.C.-Pad2)") (class "Default")
      (node (ref "Z3") (pin "2") (pinfunction "N.C._2") (pintype "passive+no_connect"))
    )
    (net (code "64") (name "unconnected-(Z4-N.C.-Pad2)") (class "Default")
      (node (ref "Z4") (pin "2") (pinfunction "N.C._2") (pintype "passive+no_connect"))
    )
  )
)
